# ItsyBitsy_Display_Add-On.net
KiCad netlist of a schematic drawn in EAGLE
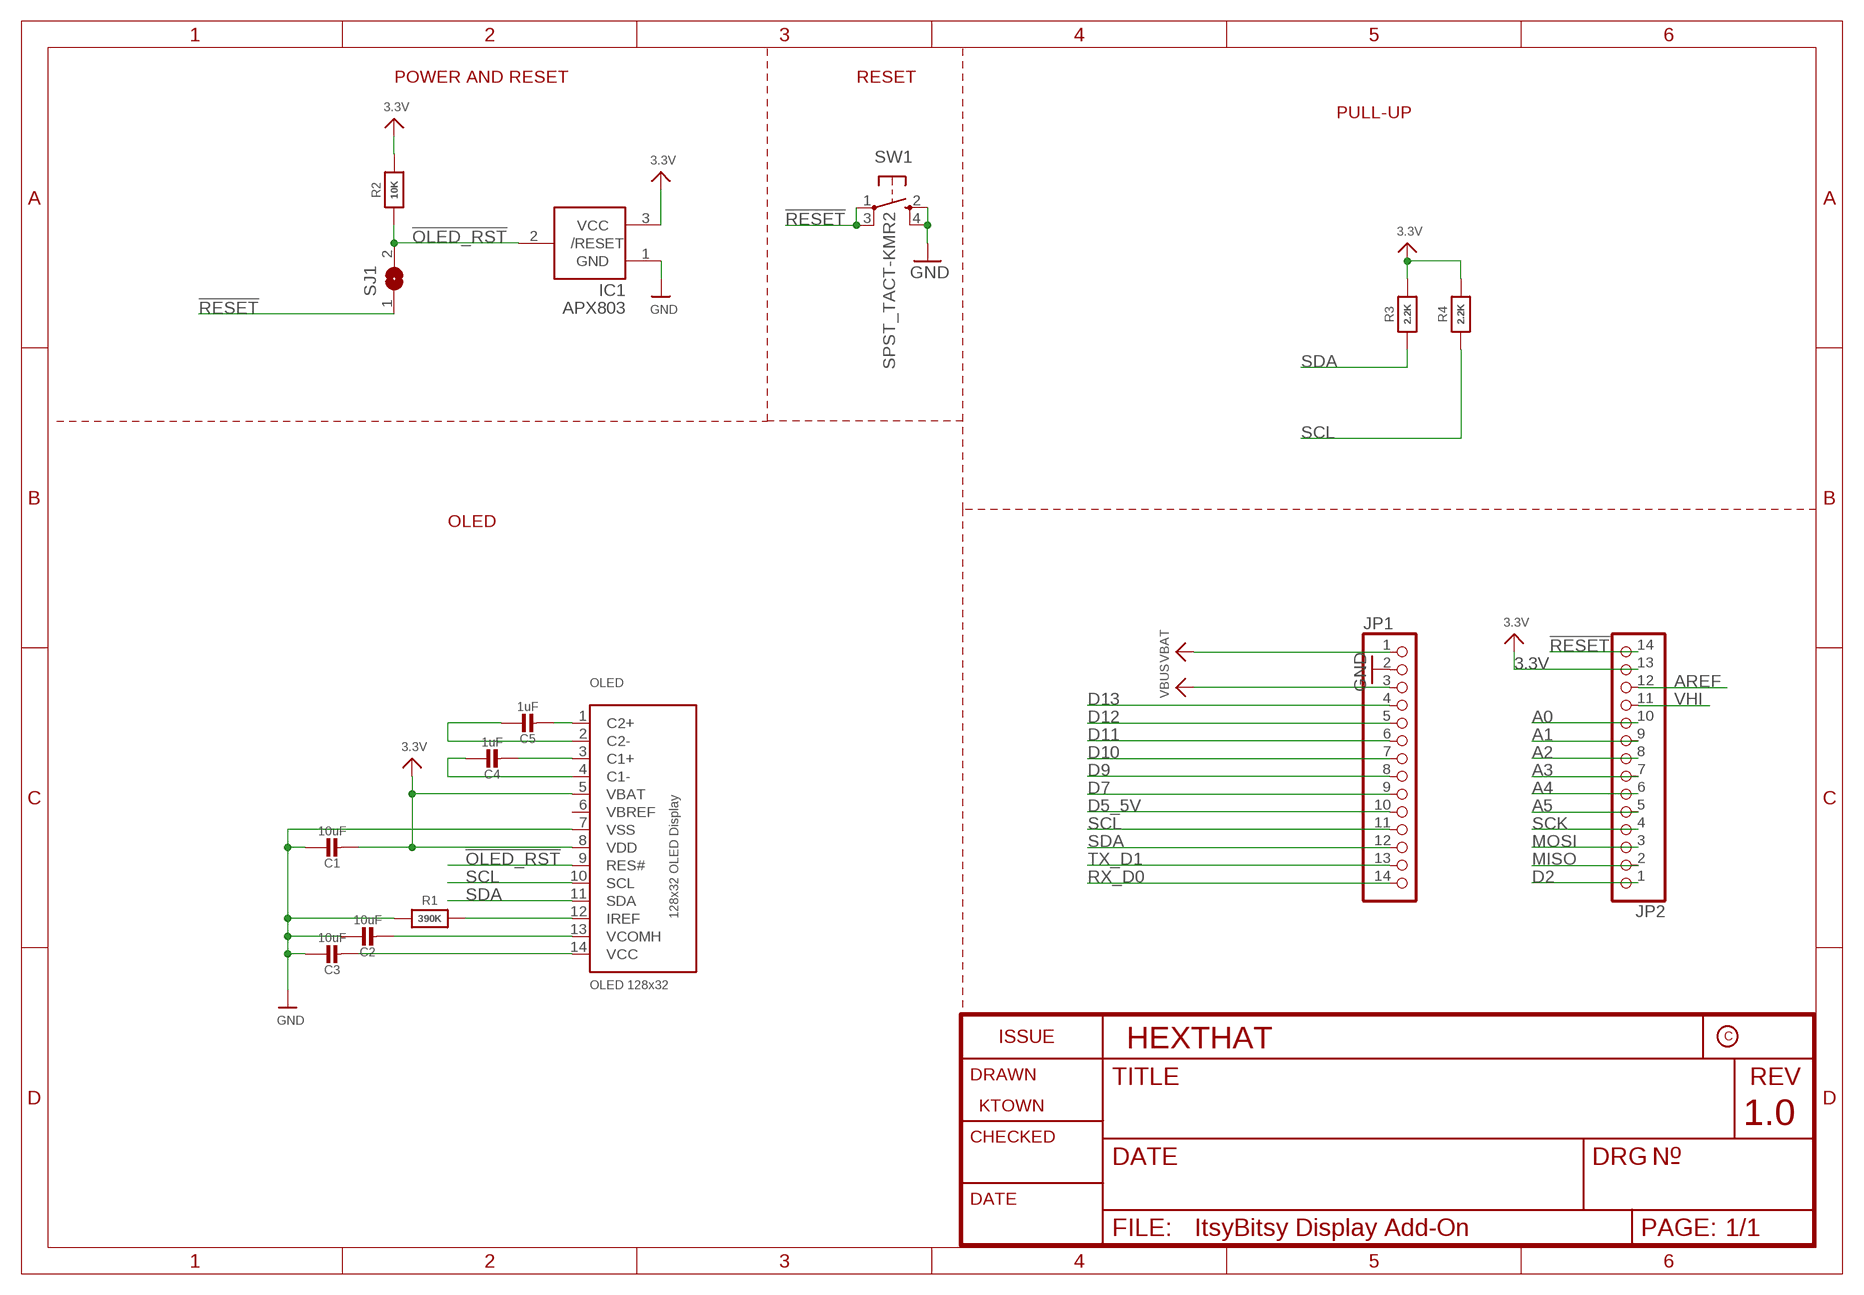
[diagram p0: schematic, sheet 1]

(export (version "E")
  (design (tool "Eeschema 10.0.6"))
  (components
    (comp (ref "C1")
      (value "10uF")
      (footprint "eagle-import:0805-NO")
      (libsource (lib "eagle-import") (part "CAP_CERAMIC0805-NOOUTLINE"))
    )
    (comp (ref "C2")
      (value "10uF")
      (footprint "eagle-import:0805-NO")
      (libsource (lib "eagle-import") (part "CAP_CERAMIC0805-NOOUTLINE"))
    )
    (comp (ref "C3")
      (value "10uF")
      (footprint "eagle-import:0805-NO")
      (libsource (lib "eagle-import") (part "CAP_CERAMIC0805-NOOUTLINE"))
    )
    (comp (ref "C4")
      (value "1uF")
      (footprint "eagle-import:0805-NO")
      (libsource (lib "eagle-import") (part "CAP_CERAMIC0805-NOOUTLINE"))
    )
    (comp (ref "C5")
      (value "1uF")
      (footprint "eagle-import:0805-NO")
      (libsource (lib "eagle-import") (part "CAP_CERAMIC0805-NOOUTLINE"))
    )
    (comp (ref "IC1")
      (value "APX803")
      (footprint "eagle-import:SOT23")
      (libsource (lib "eagle-import") (part "AXP083-SAG"))
    )
    (comp (ref "JP1")
      (value "HEADER-1X14")
      (footprint "eagle-import:1X14_ROUND70")
      (libsource (lib "eagle-import") (part "HEADER-1X14"))
    )
    (comp (ref "JP2")
      (value "HEADER-1X14")
      (footprint "eagle-import:1X14_ROUND70")
      (libsource (lib "eagle-import") (part "HEADER-1X14"))
    )
    (comp (ref "OLED")
      (value "OLED 128x32")
      (footprint "eagle-import:UG-2832HSWEG02_WRAPUNDER")
      (libsource (lib "eagle-import") (part "DISP_OLED_UG-2832HSWEG02"))
    )
    (comp (ref "R1")
      (value "390K")
      (footprint "eagle-import:0805-NO")
      (libsource (lib "eagle-import") (part "RESISTOR0805_NOOUTLINE"))
    )
    (comp (ref "R2")
      (value "10K")
      (footprint "eagle-import:_0805MP")
      (libsource (lib "eagle-import") (part "RESISTOR_0805MP"))
    )
    (comp (ref "R3")
      (value "2.2K")
      (footprint "eagle-import:0805-NO")
      (libsource (lib "eagle-import") (part "RESISTOR0805_NOOUTLINE"))
    )
    (comp (ref "R4")
      (value "2.2K")
      (footprint "eagle-import:0805-NO")
      (libsource (lib "eagle-import") (part "RESISTOR0805_NOOUTLINE"))
    )
    (comp (ref "SJ1")
      (value "SOLDERJUMPER")
      (footprint "eagle-import:SOLDERJUMPER_ARROW_NOPASTE")
      (libsource (lib "eagle-import") (part "SOLDERJUMPER"))
    )
    (comp (ref "SW1")
      (value "SPST_TACT-KMR2")
      (footprint "eagle-import:KMR2")
      (libsource (lib "eagle-import") (part "SPST_TACT-KMR2"))
    )
  )
  (nets
    (net (code "1") (name "/A0") (class "Default")
      (node (ref "JP2") (pin "10") (pinfunction "10_10") (pintype "passive"))
    )
    (net (code "2") (name "/A1") (class "Default")
      (node (ref "JP2") (pin "9") (pinfunction "9_9") (pintype "passive"))
    )
    (net (code "3") (name "/A2") (class "Default")
      (node (ref "JP2") (pin "8") (pinfunction "8_8") (pintype "passive"))
    )
    (net (code "4") (name "/A3") (class "Default")
      (node (ref "JP2") (pin "7") (pinfunction "7_7") (pintype "passive"))
    )
    (net (code "5") (name "/A4") (class "Default")
      (node (ref "JP2") (pin "6") (pinfunction "6_6") (pintype "passive"))
    )
    (net (code "6") (name "/A5") (class "Default")
      (node (ref "JP2") (pin "5") (pinfunction "5_5") (pintype "passive"))
    )
    (net (code "7") (name "/AREF") (class "Default")
      (node (ref "JP2") (pin "12") (pinfunction "12_12") (pintype "passive"))
    )
    (net (code "8") (name "/D2") (class "Default")
      (node (ref "JP2") (pin "1") (pinfunction "1_1") (pintype "passive"))
    )
    (net (code "9") (name "/D5_5V") (class "Default")
      (node (ref "JP1") (pin "10") (pinfunction "10_10") (pintype "passive"))
    )
    (net (code "10") (name "/D7") (class "Default")
      (node (ref "JP1") (pin "9") (pinfunction "9_9") (pintype "passive"))
    )
    (net (code "11") (name "/D9") (class "Default")
      (node (ref "JP1") (pin "8") (pinfunction "8_8") (pintype "passive"))
    )
    (net (code "12") (name "/D10") (class "Default")
      (node (ref "JP1") (pin "7") (pinfunction "7_7") (pintype "passive"))
    )
    (net (code "13") (name "/D11") (class "Default")
      (node (ref "JP1") (pin "6") (pinfunction "6_6") (pintype "passive"))
    )
    (net (code "14") (name "/D12") (class "Default")
      (node (ref "JP1") (pin "5") (pinfunction "5_5") (pintype "passive"))
    )
    (net (code "15") (name "/D13") (class "Default")
      (node (ref "JP1") (pin "4") (pinfunction "4_4") (pintype "passive"))
    )
    (net (code "16") (name "/MISO") (class "Default")
      (node (ref "JP2") (pin "2") (pinfunction "2_2") (pintype "passive"))
    )
    (net (code "17") (name "/MOSI") (class "Default")
      (node (ref "JP2") (pin "3") (pinfunction "3_3") (pintype "passive"))
    )
    (net (code "18") (name "/RX_D0") (class "Default")
      (node (ref "JP1") (pin "14") (pinfunction "14_14") (pintype "passive"))
    )
    (net (code "19") (name "/SCK") (class "Default")
      (node (ref "JP2") (pin "4") (pinfunction "4_4") (pintype "passive"))
    )
    (net (code "20") (name "/SCL") (class "Default")
      (node (ref "JP1") (pin "11") (pinfunction "11_11") (pintype "passive"))
      (node (ref "OLED") (pin "10") (pinfunction "SCL_10") (pintype "bidirectional"))
      (node (ref "R4") (pin "1") (pinfunction "1_1") (pintype "passive"))
    )
    (net (code "21") (name "/SDA") (class "Default")
      (node (ref "JP1") (pin "12") (pinfunction "12_12") (pintype "passive"))
      (node (ref "OLED") (pin "11") (pinfunction "SDA_11") (pintype "bidirectional"))
      (node (ref "R3") (pin "1") (pinfunction "1_1") (pintype "passive"))
    )
    (net (code "22") (name "/TX_D1") (class "Default")
      (node (ref "JP1") (pin "13") (pinfunction "13_13") (pintype "passive"))
    )
    (net (code "23") (name "/VBREF") (class "Default")
      (node (ref "OLED") (pin "6") (pinfunction "VBREF_6") (pintype "power_in"))
    )
    (net (code "24") (name "/VHI") (class "Default")
      (node (ref "JP2") (pin "11") (pinfunction "11_11") (pintype "passive"))
    )
    (net (code "25") (name "/~{OLED_RST}") (class "Default")
      (node (ref "IC1") (pin "2") (pinfunction "/RESET_2") (pintype "output"))
      (node (ref "OLED") (pin "9") (pinfunction "RES#_9") (pintype "bidirectional"))
      (node (ref "R2") (pin "1") (pinfunction "1_1") (pintype "passive"))
      (node (ref "SJ1") (pin "2") (pinfunction "2_2") (pintype "passive"))
    )
    (net (code "26") (name "/~{RESET}") (class "Default")
      (node (ref "JP2") (pin "14") (pinfunction "14_14") (pintype "passive"))
      (node (ref "SJ1") (pin "1") (pinfunction "1_1") (pintype "passive"))
      (node (ref "SW1") (pin "1") (pinfunction "P_1") (pintype "passive"))
      (node (ref "SW1") (pin "3") (pinfunction "P1_3") (pintype "passive"))
    )
    (net (code "27") (name "3.3V") (class "Default")
      (node (ref "C1") (pin "2") (pinfunction "2_2") (pintype "passive"))
      (node (ref "IC1") (pin "3") (pinfunction "VCC_3") (pintype "power_in"))
      (node (ref "JP2") (pin "13") (pinfunction "13_13") (pintype "passive"))
      (node (ref "OLED") (pin "5") (pinfunction "VBAT_5") (pintype "power_in"))
      (node (ref "OLED") (pin "8") (pinfunction "VDD_8") (pintype "power_in"))
      (node (ref "R2") (pin "2") (pinfunction "2_2") (pintype "passive"))
      (node (ref "R3") (pin "2") (pinfunction "2_2") (pintype "passive"))
      (node (ref "R4") (pin "2") (pinfunction "2_2") (pintype "passive"))
    )
    (net (code "28") (name "GND") (class "Default")
      (node (ref "C1") (pin "1") (pinfunction "1_1") (pintype "passive"))
      (node (ref "C2") (pin "1") (pinfunction "1_1") (pintype "passive"))
      (node (ref "C3") (pin "1") (pinfunction "1_1") (pintype "passive"))
      (node (ref "IC1") (pin "1") (pinfunction "GND_1") (pintype "power_in"))
      (node (ref "JP1") (pin "2") (pinfunction "2_2") (pintype "passive"))
      (node (ref "OLED") (pin "7") (pinfunction "VSS_7") (pintype "power_in"))
      (node (ref "R1") (pin "1") (pinfunction "1_1") (pintype "passive"))
      (node (ref "SW1") (pin "2") (pinfunction "S_2") (pintype "passive"))
      (node (ref "SW1") (pin "4") (pinfunction "S1_4") (pintype "passive"))
    )
    (net (code "29") (name "Net-(OLED-C1+)") (class "Default")
      (node (ref "C4") (pin "2") (pinfunction "2_2") (pintype "passive"))
      (node (ref "OLED") (pin "3") (pinfunction "C1+_3") (pintype "bidirectional"))
    )
    (net (code "30") (name "Net-(OLED-C1-)") (class "Default")
      (node (ref "C4") (pin "1") (pinfunction "1_1") (pintype "passive"))
      (node (ref "OLED") (pin "4") (pinfunction "C1-_4") (pintype "bidirectional"))
    )
    (net (code "31") (name "Net-(OLED-C2+)") (class "Default")
      (node (ref "C5") (pin "2") (pinfunction "2_2") (pintype "passive"))
      (node (ref "OLED") (pin "1") (pinfunction "C2+_1") (pintype "bidirectional"))
    )
    (net (code "32") (name "Net-(OLED-C2-)") (class "Default")
      (node (ref "C5") (pin "1") (pinfunction "1_1") (pintype "passive"))
      (node (ref "OLED") (pin "2") (pinfunction "C2-_2") (pintype "bidirectional"))
    )
    (net (code "33") (name "Net-(OLED-IREF)") (class "Default")
      (node (ref "OLED") (pin "12") (pinfunction "IREF_12") (pintype "bidirectional"))
      (node (ref "R1") (pin "2") (pinfunction "2_2") (pintype "passive"))
    )
    (net (code "34") (name "Net-(OLED-VCC)") (class "Default")
      (node (ref "C3") (pin "2") (pinfunction "2_2") (pintype "passive"))
      (node (ref "OLED") (pin "14") (pinfunction "VCC_14") (pintype "power_in"))
    )
    (net (code "35") (name "Net-(OLED-VCOMH)") (class "Default")
      (node (ref "C2") (pin "2") (pinfunction "2_2") (pintype "passive"))
      (node (ref "OLED") (pin "13") (pinfunction "VCOMH_13") (pintype "power_in"))
    )
    (net (code "36") (name "VBAT") (class "Default")
      (node (ref "JP1") (pin "1") (pinfunction "1_1") (pintype "passive"))
    )
    (net (code "37") (name "VBUS") (class "Default")
      (node (ref "JP1") (pin "3") (pinfunction "3_3") (pintype "passive"))
    )
  )
)
